# PB.net
KiCad netlist of a schematic drawn in EAGLE
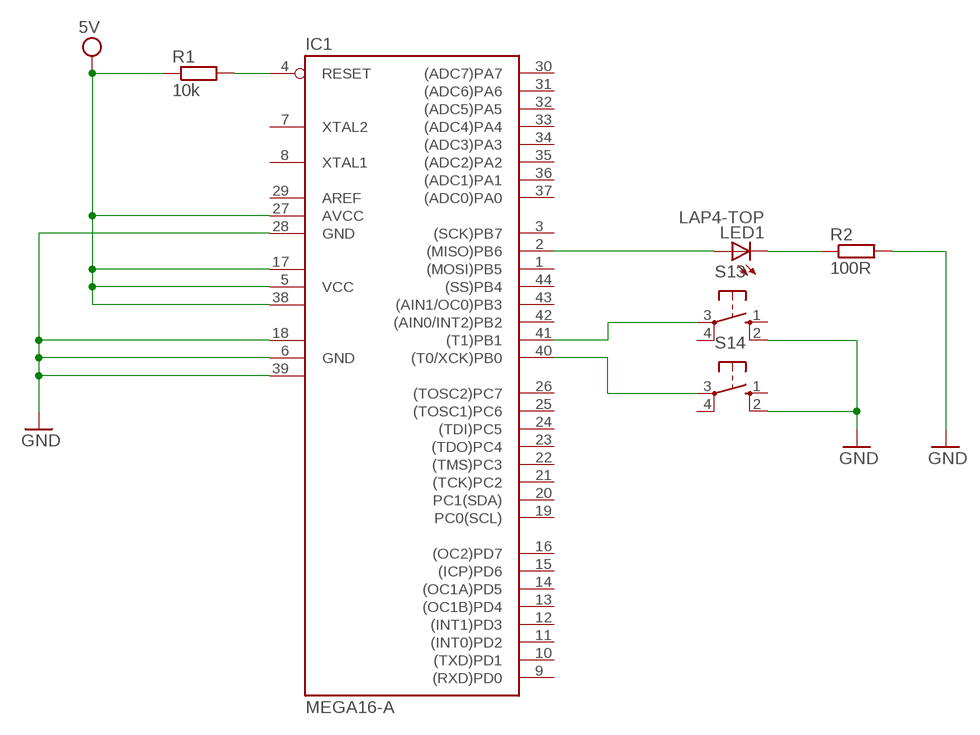
[diagram p0: schematic, sheet 1]

(export (version "E")
  (design (tool "Eeschema 10.0.6"))
  (components
    (comp (ref "IC1")
      (value "MEGA16-A")
      (footprint "eagle-import:TQFP44")
      (fields (field (name "MPN") "ATMEGA16-16AU"))
      (libsource (lib "eagle-import") (part "MEGA16-A"))
    )
    (comp (ref "LED1")
      (value "LAP4-TOP")
      (footprint "eagle-import:P47F-TOP")
      (libsource (lib "eagle-import") (part "P4-TOPLA"))
    )
    (comp (ref "R1")
      (value "10k")
      (footprint "eagle-import:M0805")
      (libsource (lib "eagle-import") (part "R-EU_M0805"))
    )
    (comp (ref "R2")
      (value "100R")
      (footprint "eagle-import:M0805")
      (libsource (lib "eagle-import") (part "R-EU_M0805"))
    )
    (comp (ref "S13")
      (value "40/XX")
      (footprint "eagle-import:B3F_40XX")
      (libsource (lib "eagle-import") (part "40/XX"))
    )
    (comp (ref "S14")
      (value "40/XX")
      (footprint "eagle-import:B3F_40XX")
      (libsource (lib "eagle-import") (part "40/XX"))
    )
  )
  (nets
    (net (code "1") (name "5V") (class "Default")
      (node (ref "IC1") (pin "17") (pinfunction "VCC1_17") (pintype "power_in"))
      (node (ref "IC1") (pin "27") (pinfunction "AVCC_27") (pintype "power_in"))
      (node (ref "IC1") (pin "38") (pinfunction "VCC2_38") (pintype "power_in"))
      (node (ref "IC1") (pin "5") (pinfunction "VCC_5") (pintype "power_in"))
      (node (ref "R1") (pin "1") (pinfunction "1_1") (pintype "passive"))
    )
    (net (code "2") (name "GND") (class "Default")
      (node (ref "IC1") (pin "18") (pinfunction "GND1_18") (pintype "power_in"))
      (node (ref "IC1") (pin "28") (pinfunction "GND_28") (pintype "power_in"))
      (node (ref "IC1") (pin "39") (pinfunction "GND2_39") (pintype "power_in"))
      (node (ref "IC1") (pin "6") (pinfunction "GND_6") (pintype "power_in"))
      (node (ref "R2") (pin "2") (pinfunction "2_2") (pintype "passive"))
      (node (ref "S13") (pin "2") (pinfunction "S1_2") (pintype "passive"))
      (node (ref "S14") (pin "2") (pinfunction "S1_2") (pintype "passive"))
    )
    (net (code "3") (name "Net-(IC1-(MISO)PB6)") (class "Default")
      (node (ref "IC1") (pin "2") (pinfunction "(MISO)PB6_2") (pintype "bidirectional"))
      (node (ref "LED1") (pin "A") (pinfunction "A_A") (pintype "passive"))
    )
    (net (code "4") (name "Net-(IC1-(T0{slash}XCK)PB0)") (class "Default")
      (node (ref "IC1") (pin "40") (pinfunction "(T0/XCK)PB0_40") (pintype "bidirectional"))
      (node (ref "S14") (pin "3") (pinfunction "P_3") (pintype "passive"))
    )
    (net (code "5") (name "Net-(IC1-(T1)PB1)") (class "Default")
      (node (ref "IC1") (pin "41") (pinfunction "(T1)PB1_41") (pintype "bidirectional"))
      (node (ref "S13") (pin "3") (pinfunction "P_3") (pintype "passive"))
    )
    (net (code "6") (name "Net-(IC1-RESET)") (class "Default")
      (node (ref "IC1") (pin "4") (pinfunction "RESET_4") (pintype "input"))
      (node (ref "R1") (pin "2") (pinfunction "2_2") (pintype "passive"))
    )
    (net (code "7") (name "Net-(LED1-PadC)") (class "Default")
      (node (ref "LED1") (pin "C") (pinfunction "C_C") (pintype "passive"))
      (node (ref "R2") (pin "1") (pinfunction "1_1") (pintype "passive"))
    )
    (net (code "8") (name "unconnected-(IC1-(ADC0)PA0-Pad37)") (class "Default")
      (node (ref "IC1") (pin "37") (pinfunction "(ADC0)PA0_37") (pintype "bidirectional"))
    )
    (net (code "9") (name "unconnected-(IC1-(ADC1)PA1-Pad36)") (class "Default")
      (node (ref "IC1") (pin "36") (pinfunction "(ADC1)PA1_36") (pintype "bidirectional"))
    )
    (net (code "10") (name "unconnected-(IC1-(ADC2)PA2-Pad35)") (class "Default")
      (node (ref "IC1") (pin "35") (pinfunction "(ADC2)PA2_35") (pintype "bidirectional"))
    )
    (net (code "11") (name "unconnected-(IC1-(ADC3)PA3-Pad34)") (class "Default")
      (node (ref "IC1") (pin "34") (pinfunction "(ADC3)PA3_34") (pintype "bidirectional"))
    )
    (net (code "12") (name "unconnected-(IC1-(ADC4)PA4-Pad33)") (class "Default")
      (node (ref "IC1") (pin "33") (pinfunction "(ADC4)PA4_33") (pintype "bidirectional"))
    )
    (net (code "13") (name "unconnected-(IC1-(ADC5)PA5-Pad32)") (class "Default")
      (node (ref "IC1") (pin "32") (pinfunction "(ADC5)PA5_32") (pintype "bidirectional"))
    )
    (net (code "14") (name "unconnected-(IC1-(ADC6)PA6-Pad31)") (class "Default")
      (node (ref "IC1") (pin "31") (pinfunction "(ADC6)PA6_31") (pintype "bidirectional"))
    )
    (net (code "15") (name "unconnected-(IC1-(ADC7)PA7-Pad30)") (class "Default")
      (node (ref "IC1") (pin "30") (pinfunction "(ADC7)PA7_30") (pintype "bidirectional"))
    )
    (net (code "16") (name "unconnected-(IC1-(AIN0{slash}INT2)PB2-Pad42)") (class "Default")
      (node (ref "IC1") (pin "42") (pinfunction "(AIN0/INT2)PB2_42") (pintype "bidirectional"))
    )
    (net (code "17") (name "unconnected-(IC1-(AIN1{slash}OC0)PB3-Pad43)") (class "Default")
      (node (ref "IC1") (pin "43") (pinfunction "(AIN1/OC0)PB3_43") (pintype "bidirectional"))
    )
    (net (code "18") (name "unconnected-(IC1-(ICP)PD6-Pad15)") (class "Default")
      (node (ref "IC1") (pin "15") (pinfunction "(ICP)PD6_15") (pintype "bidirectional"))
    )
    (net (code "19") (name "unconnected-(IC1-(INT0)PD2-Pad11)") (class "Default")
      (node (ref "IC1") (pin "11") (pinfunction "(INT0)PD2_11") (pintype "bidirectional"))
    )
    (net (code "20") (name "unconnected-(IC1-(INT1)PD3-Pad12)") (class "Default")
      (node (ref "IC1") (pin "12") (pinfunction "(INT1)PD3_12") (pintype "bidirectional"))
    )
    (net (code "21") (name "unconnected-(IC1-(MOSI)PB5-Pad1)") (class "Default")
      (node (ref "IC1") (pin "1") (pinfunction "(MOSI)PB5_1") (pintype "bidirectional"))
    )
    (net (code "22") (name "unconnected-(IC1-(OC1A)PD5-Pad14)") (class "Default")
      (node (ref "IC1") (pin "14") (pinfunction "(OC1A)PD5_14") (pintype "bidirectional"))
    )
    (net (code "23") (name "unconnected-(IC1-(OC1B)PD4-Pad13)") (class "Default")
      (node (ref "IC1") (pin "13") (pinfunction "(OC1B)PD4_13") (pintype "bidirectional"))
    )
    (net (code "24") (name "unconnected-(IC1-(OC2)PD7-Pad16)") (class "Default")
      (node (ref "IC1") (pin "16") (pinfunction "(OC2)PD7_16") (pintype "bidirectional"))
    )
    (net (code "25") (name "unconnected-(IC1-(RXD)PD0-Pad9)") (class "Default")
      (node (ref "IC1") (pin "9") (pinfunction "(RXD)PD0_9") (pintype "bidirectional"))
    )
    (net (code "26") (name "unconnected-(IC1-(SCK)PB7-Pad3)") (class "Default")
      (node (ref "IC1") (pin "3") (pinfunction "(SCK)PB7_3") (pintype "bidirectional"))
    )
    (net (code "27") (name "unconnected-(IC1-(SS)PB4-Pad44)") (class "Default")
      (node (ref "IC1") (pin "44") (pinfunction "(SS)PB4_44") (pintype "bidirectional"))
    )
    (net (code "28") (name "unconnected-(IC1-(TCK)PC2-Pad21)") (class "Default")
      (node (ref "IC1") (pin "21") (pinfunction "(TCK)PC2_21") (pintype "bidirectional"))
    )
    (net (code "29") (name "unconnected-(IC1-(TDI)PC5-Pad24)") (class "Default")
      (node (ref "IC1") (pin "24") (pinfunction "(TDI)PC5_24") (pintype "bidirectional"))
    )
    (net (code "30") (name "unconnected-(IC1-(TDO)PC4-Pad23)") (class "Default")
      (node (ref "IC1") (pin "23") (pinfunction "(TDO)PC4_23") (pintype "bidirectional"))
    )
    (net (code "31") (name "unconnected-(IC1-(TMS)PC3-Pad22)") (class "Default")
      (node (ref "IC1") (pin "22") (pinfunction "(TMS)PC3_22") (pintype "bidirectional"))
    )
    (net (code "32") (name "unconnected-(IC1-(TOSC1)PC6-Pad25)") (class "Default")
      (node (ref "IC1") (pin "25") (pinfunction "(TOSC1)PC6_25") (pintype "bidirectional"))
    )
    (net (code "33") (name "unconnected-(IC1-(TOSC2)PC7-Pad26)") (class "Default")
      (node (ref "IC1") (pin "26") (pinfunction "(TOSC2)PC7_26") (pintype "bidirectional"))
    )
    (net (code "34") (name "unconnected-(IC1-(TXD)PD1-Pad10)") (class "Default")
      (node (ref "IC1") (pin "10") (pinfunction "(TXD)PD1_10") (pintype "bidirectional"))
    )
    (net (code "35") (name "unconnected-(IC1-AREF-Pad29)") (class "Default")
      (node (ref "IC1") (pin "29") (pinfunction "AREF_29") (pintype "passive"))
    )
    (net (code "36") (name "unconnected-(IC1-PC0(SCL)-Pad19)") (class "Default")
      (node (ref "IC1") (pin "19") (pinfunction "PC0(SCL)_19") (pintype "bidirectional"))
    )
    (net (code "37") (name "unconnected-(IC1-PC1(SDA)-Pad20)") (class "Default")
      (node (ref "IC1") (pin "20") (pinfunction "PC1(SDA)_20") (pintype "bidirectional"))
    )
    (net (code "38") (name "unconnected-(IC1-XTAL1-Pad8)") (class "Default")
      (node (ref "IC1") (pin "8") (pinfunction "XTAL1_8") (pintype "bidirectional"))
    )
    (net (code "39") (name "unconnected-(IC1-XTAL2-Pad7)") (class "Default")
      (node (ref "IC1") (pin "7") (pinfunction "XTAL2_7") (pintype "bidirectional"))
    )
    (net (code "40") (name "unconnected-(S13-P1-Pad4)") (class "Default")
      (node (ref "S13") (pin "4") (pinfunction "P1_4") (pintype "passive"))
    )
    (net (code "41") (name "unconnected-(S13-S-Pad1)") (class "Default")
      (node (ref "S13") (pin "1") (pinfunction "S_1") (pintype "passive"))
    )
    (net (code "42") (name "unconnected-(S14-P1-Pad4)") (class "Default")
      (node (ref "S14") (pin "4") (pinfunction "P1_4") (pintype "passive"))
    )
    (net (code "43") (name "unconnected-(S14-S-Pad1)") (class "Default")
      (node (ref "S14") (pin "1") (pinfunction "S_1") (pintype "passive"))
    )
  )
)
